# RTDS.net
KiCad netlist of a schematic drawn in EAGLE
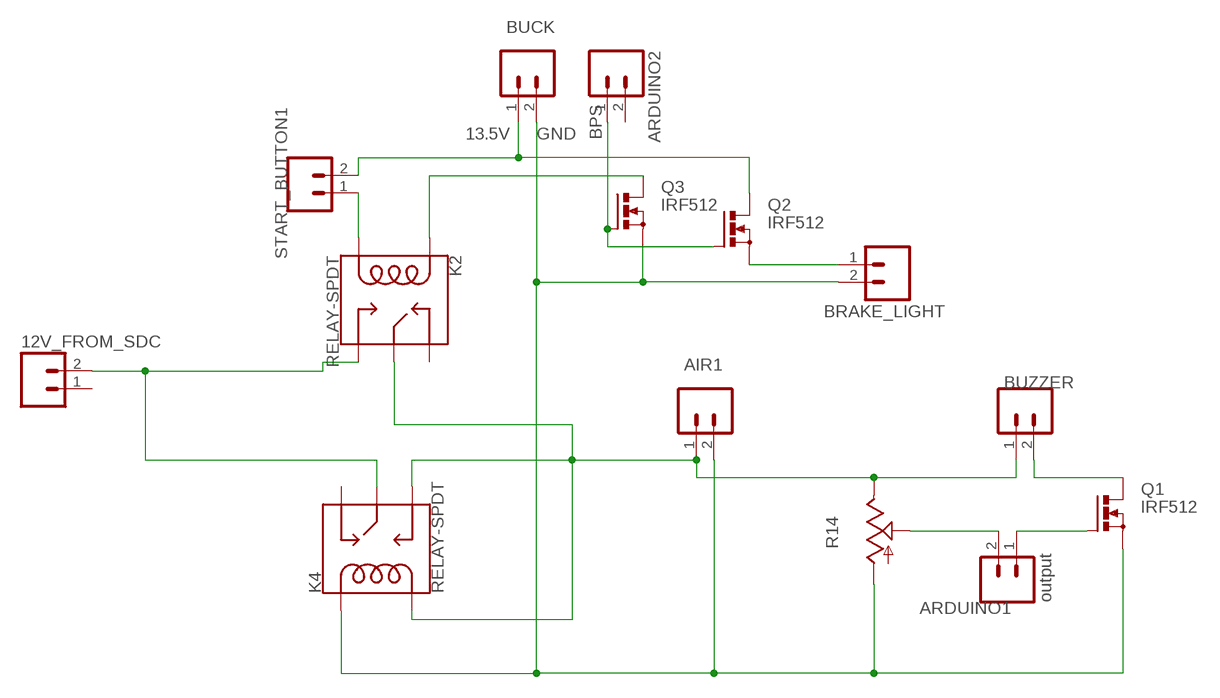
[diagram p0: schematic, sheet 1]

(export (version "E")
  (design (tool "Eeschema 10.0.6"))
  (components
    (comp (ref "12V_FROM_SDC")
      (value "M02")
      (footprint "eagle-import:02P")
      (libsource (lib "eagle-import") (part "M02"))
    )
    (comp (ref "AIR1")
      (value "M02")
      (footprint "eagle-import:02P")
      (libsource (lib "eagle-import") (part "M02"))
    )
    (comp (ref "ARDUINO1")
      (value "output")
      (footprint "eagle-import:02P")
      (libsource (lib "eagle-import") (part "M02"))
    )
    (comp (ref "ARDUINO2")
      (value "BPS")
      (footprint "eagle-import:02P")
      (libsource (lib "eagle-import") (part "M02"))
    )
    (comp (ref "BRAKE_LIGHT")
      (value "M02")
      (footprint "eagle-import:02P")
      (libsource (lib "eagle-import") (part "M02"))
    )
    (comp (ref "BUCK")
      (value "M02")
      (footprint "eagle-import:02P")
      (libsource (lib "eagle-import") (part "M02"))
    )
    (comp (ref "BUZZER")
      (value "M02")
      (footprint "eagle-import:02P")
      (libsource (lib "eagle-import") (part "M02"))
    )
    (comp (ref "K2")
      (value "RELAY-SPDT")
      (footprint "eagle-import:RELAY_G5LE")
      (libsource (lib "eagle-import") (part "RELAY-SPDT"))
    )
    (comp (ref "K4")
      (value "RELAY-SPDT")
      (footprint "eagle-import:RELAY_G5LE")
      (libsource (lib "eagle-import") (part "RELAY-SPDT"))
    )
    (comp (ref "Q1")
      (value "IRF512")
      (footprint "eagle-import:TO220BV")
      (libsource (lib "eagle-import") (part "IRF512"))
    )
    (comp (ref "Q2")
      (value "IRF512")
      (footprint "eagle-import:TO220BV")
      (libsource (lib "eagle-import") (part "IRF512"))
    )
    (comp (ref "Q3")
      (value "IRF512")
      (footprint "eagle-import:TO220BV")
      (libsource (lib "eagle-import") (part "IRF512"))
    )
    (comp (ref "R14")
      (value "TRIM_US-B25P")
      (footprint "eagle-import:B25P")
      (libsource (lib "eagle-import") (part "TRIM_US-B25P"))
    )
    (comp (ref "START_BUTTON1")
      (value "M02")
      (footprint "eagle-import:02P")
      (libsource (lib "eagle-import") (part "M02"))
    )
  )
  (nets
    (net (code "1") (name "/13.5V") (class "Default")
      (node (ref "BUCK") (pin "1") (pinfunction "1_1") (pintype "passive"))
      (node (ref "Q2") (pin "D") (pinfunction "D_D") (pintype "passive"))
      (node (ref "START_BUTTON1") (pin "2") (pinfunction "2_2") (pintype "passive"))
    )
    (net (code "2") (name "/GND") (class "Default")
      (node (ref "AIR1") (pin "2") (pinfunction "2_2") (pintype "passive"))
      (node (ref "BRAKE_LIGHT") (pin "2") (pinfunction "2_2") (pintype "passive"))
      (node (ref "BUCK") (pin "2") (pinfunction "2_2") (pintype "passive"))
      (node (ref "K4") (pin "2") (pinfunction "COIL1_2") (pintype "bidirectional"))
      (node (ref "Q1") (pin "S") (pinfunction "S_S") (pintype "passive"))
      (node (ref "Q3") (pin "S") (pinfunction "S_S") (pintype "passive"))
      (node (ref "R14") (pin "A") (pinfunction "A_A") (pintype "passive"))
    )
    (net (code "3") (name "Net-(ARDUINO1-Pad1)") (class "Default")
      (node (ref "ARDUINO1") (pin "1") (pinfunction "1_1") (pintype "passive"))
      (node (ref "Q1") (pin "G") (pinfunction "G_G") (pintype "passive"))
    )
    (net (code "4") (name "Net-(ARDUINO1-Pad2)") (class "Default")
      (node (ref "ARDUINO1") (pin "2") (pinfunction "2_2") (pintype "passive"))
      (node (ref "R14") (pin "S") (pinfunction "S_S") (pintype "passive"))
    )
    (net (code "5") (name "Net-(ARDUINO2-Pad1)") (class "Default")
      (node (ref "ARDUINO2") (pin "1") (pinfunction "1_1") (pintype "passive"))
      (node (ref "Q2") (pin "G") (pinfunction "G_G") (pintype "passive"))
      (node (ref "Q3") (pin "G") (pinfunction "G_G") (pintype "passive"))
    )
    (net (code "6") (name "Net-(BRAKE_LIGHT-Pad1)") (class "Default")
      (node (ref "BRAKE_LIGHT") (pin "1") (pinfunction "1_1") (pintype "passive"))
      (node (ref "Q2") (pin "S") (pinfunction "S_S") (pintype "passive"))
    )
    (net (code "7") (name "Net-(BUZZER-Pad2)") (class "Default")
      (node (ref "BUZZER") (pin "2") (pinfunction "2_2") (pintype "passive"))
      (node (ref "Q1") (pin "D") (pinfunction "D_D") (pintype "passive"))
    )
    (net (code "8") (name "Net-(K2-COIL1)") (class "Default")
      (node (ref "K2") (pin "2") (pinfunction "COIL1_2") (pintype "bidirectional"))
      (node (ref "Q3") (pin "D") (pinfunction "D_D") (pintype "passive"))
    )
    (net (code "9") (name "Net-(K2-COIL2)") (class "Default")
      (node (ref "K2") (pin "5") (pinfunction "COIL2_5") (pintype "bidirectional"))
      (node (ref "START_BUTTON1") (pin "1") (pinfunction "1_1") (pintype "passive"))
    )
    (net (code "10") (name "Net-(K2-MAIN)") (class "Default")
      (node (ref "AIR1") (pin "1") (pinfunction "1_1") (pintype "passive"))
      (node (ref "BUZZER") (pin "1") (pinfunction "1_1") (pintype "passive"))
      (node (ref "K2") (pin "1") (pinfunction "MAIN_1") (pintype "bidirectional"))
      (node (ref "K4") (pin "3") (pinfunction "NO_3") (pintype "bidirectional"))
      (node (ref "K4") (pin "5") (pinfunction "COIL2_5") (pintype "bidirectional"))
      (node (ref "R14") (pin "E") (pinfunction "E_E") (pintype "passive"))
    )
    (net (code "11") (name "Net-(K2-NO)") (class "Default")
      (node (ref "12V_FROM_SDC") (pin "2") (pinfunction "2_2") (pintype "passive"))
      (node (ref "K2") (pin "3") (pinfunction "NO_3") (pintype "bidirectional"))
      (node (ref "K4") (pin "1") (pinfunction "MAIN_1") (pintype "bidirectional"))
    )
    (net (code "12") (name "unconnected-(12V_FROM_SDC-Pad1)") (class "Default")
      (node (ref "12V_FROM_SDC") (pin "1") (pinfunction "1_1") (pintype "passive"))
    )
    (net (code "13") (name "unconnected-(ARDUINO2-Pad2)") (class "Default")
      (node (ref "ARDUINO2") (pin "2") (pinfunction "2_2") (pintype "passive"))
    )
    (net (code "14") (name "unconnected-(K2-NC-Pad4)") (class "Default")
      (node (ref "K2") (pin "4") (pinfunction "NC_4") (pintype "bidirectional"))
    )
    (net (code "15") (name "unconnected-(K4-NC-Pad4)") (class "Default")
      (node (ref "K4") (pin "4") (pinfunction "NC_4") (pintype "bidirectional"))
    )
  )
)
